# boost-regulator.net
KiCad netlist of a schematic drawn in EAGLE
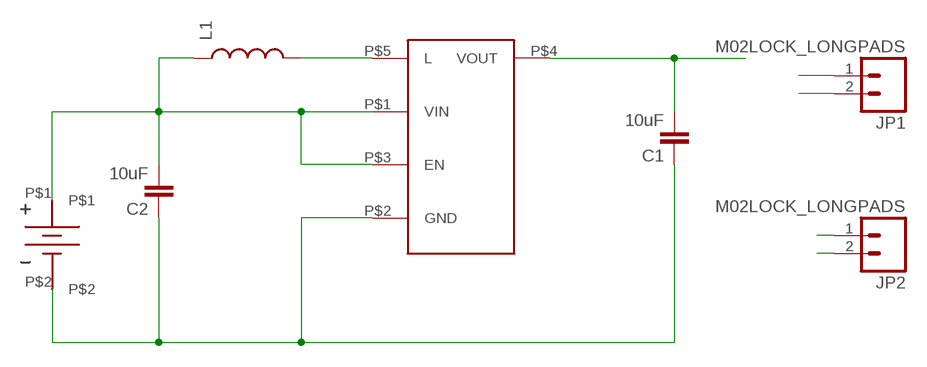
[diagram p0: schematic, sheet 1]

(export (version "E")
  (design (tool "Eeschema 10.0.6"))
  (components
    (comp (ref "C1")
      (value "10uF")
      (footprint "eagle-import:0603-CAP")
      (libsource (lib "eagle-import") (part "10UF-6.3V-20%(0603)"))
    )
    (comp (ref "C2")
      (value "10uF")
      (footprint "eagle-import:0603-CAP")
      (libsource (lib "eagle-import") (part "10UF-6.3V-20%(0603)"))
    )
    (comp (ref "JP1")
      (value "M02LOCK_LONGPADS")
      (footprint "eagle-import:1X02_LOCK_LONGPADS")
      (libsource (lib "eagle-import") (part "M02LOCK_LONGPADS"))
    )
    (comp (ref "JP2")
      (value "M02LOCK_LONGPADS")
      (footprint "eagle-import:1X02_LOCK_LONGPADS")
      (libsource (lib "eagle-import") (part "M02LOCK_LONGPADS"))
    )
    (comp (ref "L1")
      (value "INDUCTOR0603")
      (footprint "eagle-import:0603")
      (libsource (lib "eagle-import") (part "INDUCTOR0603"))
    )
    (comp (ref "U$1")
      (value "KEYSTONEAAHOLDER_2CELL")
      (footprint "eagle-import:KEYSTONEAAHOLDER_2CELL")
      (libsource (lib "eagle-import") (part "KEYSTONEAAHOLDER_2CELL"))
    )
    (comp (ref "U$2")
      (value "TPS61097-33")
      (footprint "eagle-import:SOT23-5")
      (libsource (lib "eagle-import") (part "TPS61097-33"))
    )
  )
  (nets
    (net (code "1") (name "/GND") (class "Default")
      (node (ref "C1") (pin "1") (pinfunction "1_1") (pintype "passive"))
      (node (ref "C2") (pin "1") (pinfunction "1_1") (pintype "passive"))
      (node (ref "JP1") (pin "2") (pinfunction "2_2") (pintype "passive"))
      (node (ref "JP2") (pin "2") (pinfunction "2_2") (pintype "passive"))
      (node (ref "U$1") (pin "P$2") (pinfunction "P$2_P$2") (pintype "bidirectional"))
      (node (ref "U$2") (pin "P$2") (pinfunction "GND_P$2") (pintype "bidirectional"))
    )
    (net (code "2") (name "/VCC") (class "Default")
      (node (ref "C1") (pin "2") (pinfunction "2_2") (pintype "passive"))
      (node (ref "JP1") (pin "1") (pinfunction "1_1") (pintype "passive"))
      (node (ref "JP2") (pin "1") (pinfunction "1_1") (pintype "passive"))
      (node (ref "U$2") (pin "P$4") (pinfunction "VOUT_P$4") (pintype "bidirectional"))
    )
    (net (code "3") (name "Net-(U$2-EN)") (class "Default")
      (node (ref "C2") (pin "2") (pinfunction "2_2") (pintype "passive"))
      (node (ref "L1") (pin "1") (pinfunction "1_1") (pintype "passive"))
      (node (ref "U$1") (pin "P$1") (pinfunction "P$1_P$1") (pintype "bidirectional"))
      (node (ref "U$2") (pin "P$1") (pinfunction "VIN_P$1") (pintype "bidirectional"))
      (node (ref "U$2") (pin "P$3") (pinfunction "EN_P$3") (pintype "bidirectional"))
    )
    (net (code "4") (name "Net-(U$2-L)") (class "Default")
      (node (ref "L1") (pin "2") (pinfunction "2_2") (pintype "passive"))
      (node (ref "U$2") (pin "P$5") (pinfunction "L_P$5") (pintype "bidirectional"))
    )
  )
)
